# GPIO.net
KiCad netlist of a schematic drawn in Altium Designer
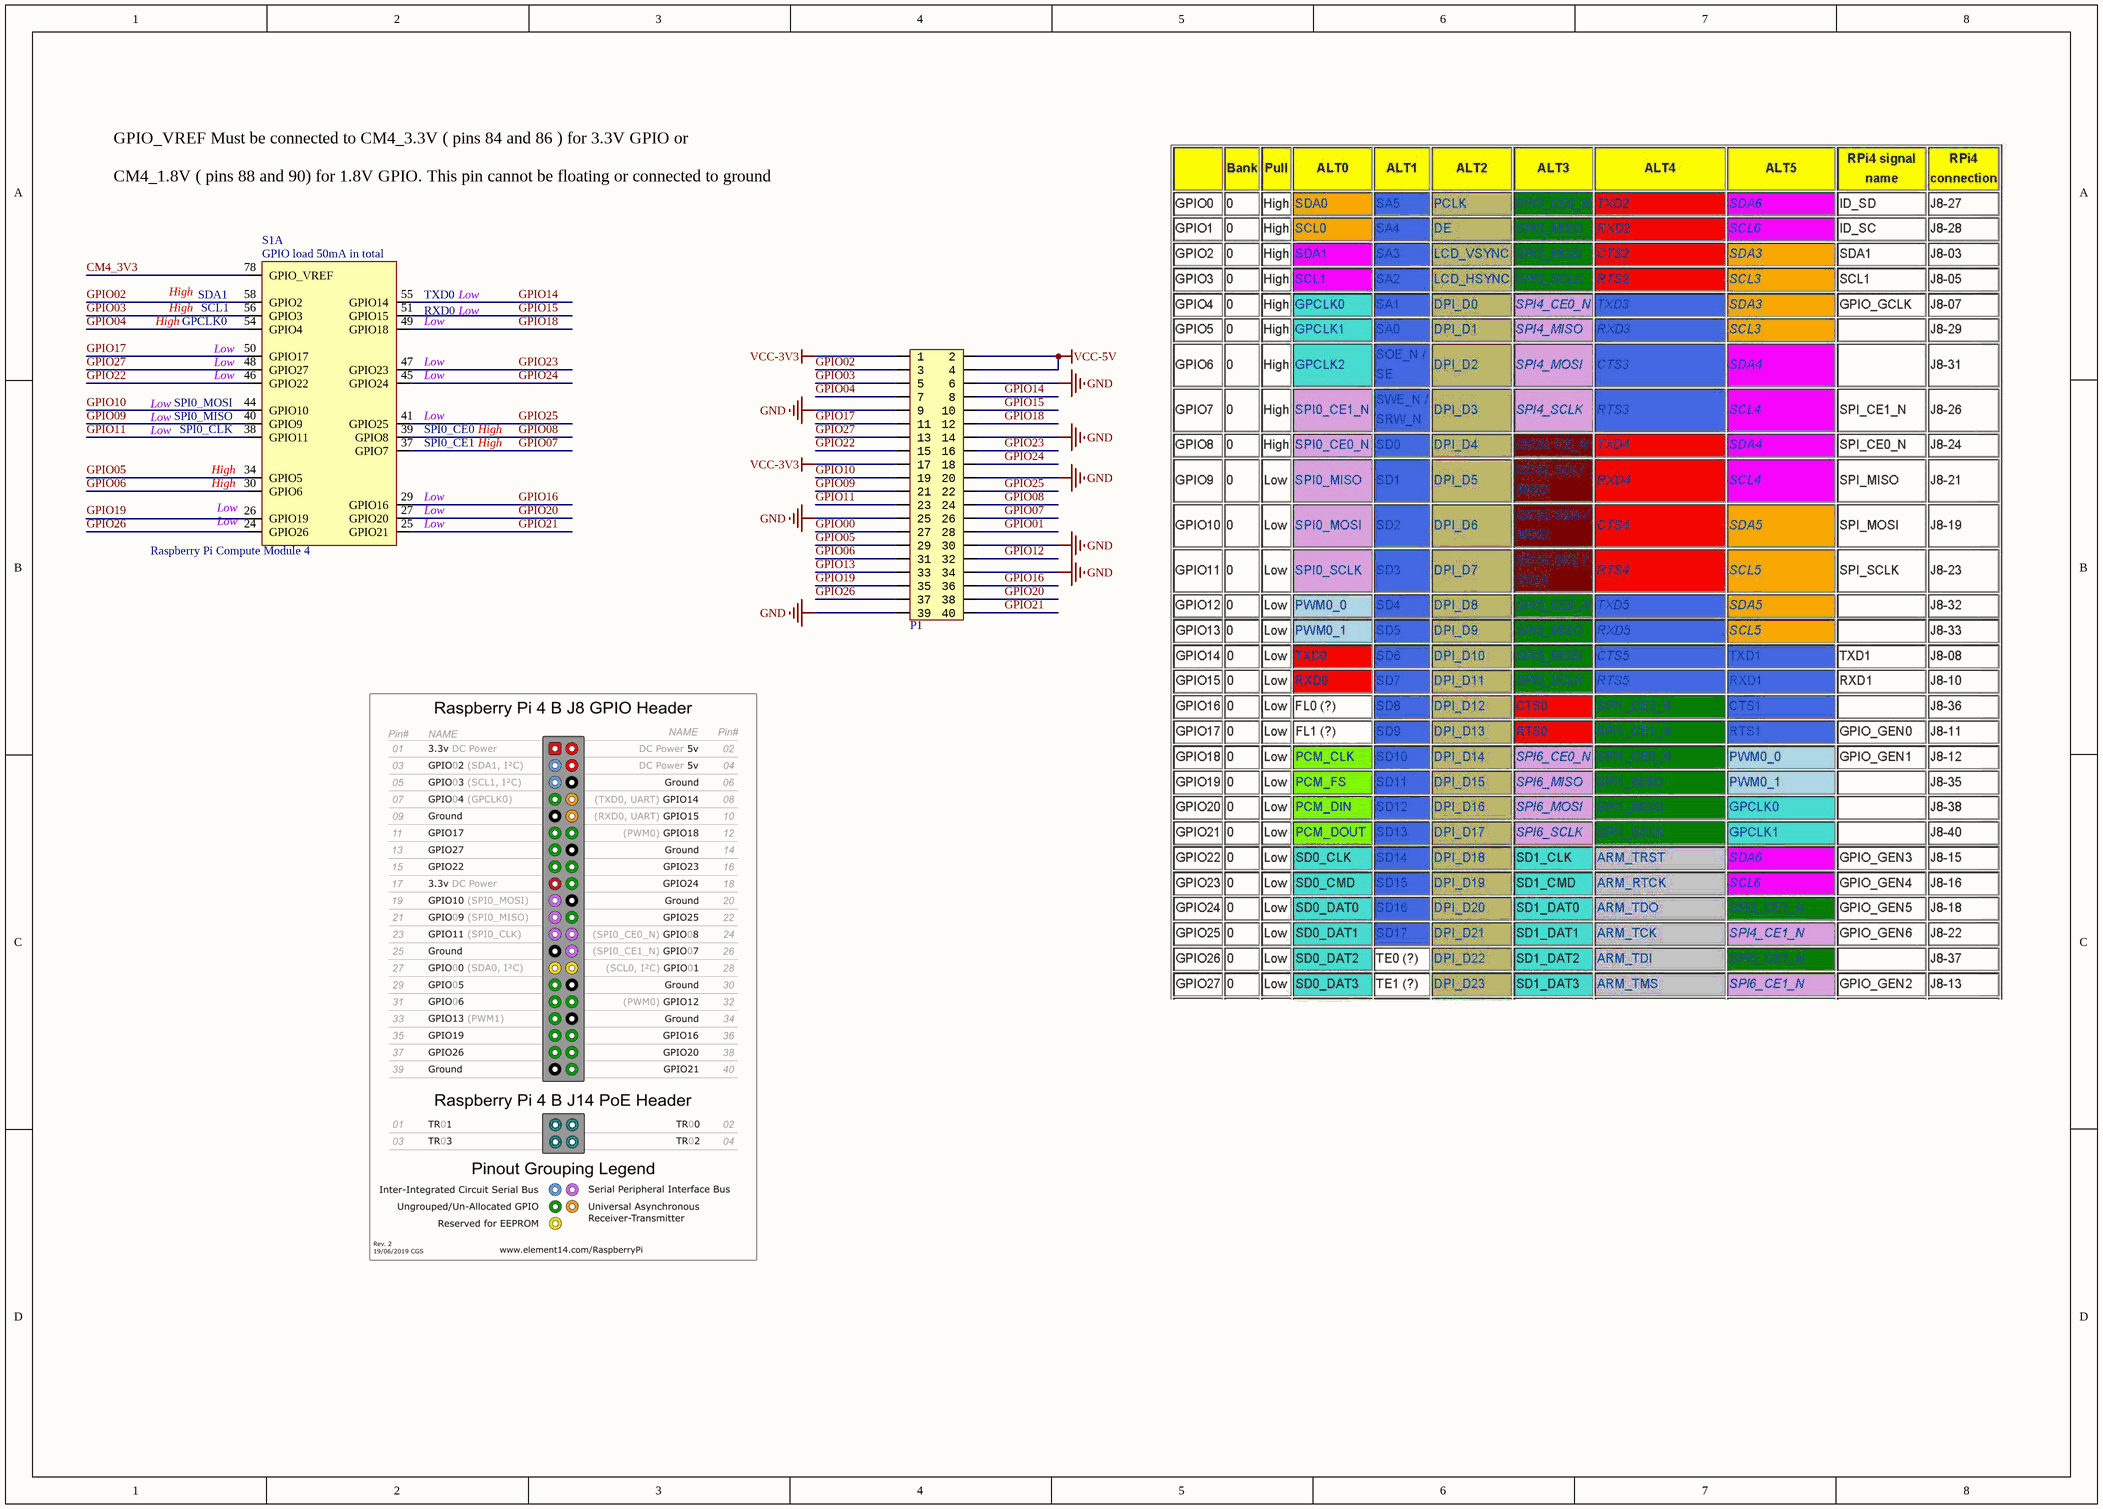
[diagram p0: GPIO.SchDoc]

(export (version "E")
  (design (tool "Eeschema 10.0.6"))
  (components
    (comp (ref "P1")
      (value "HDR2x20_2.54")
      (footprint "HDR2X20_2.54_180")
      (description "Header")
      (libsource (lib "KitSprout") (part "HDR2x20_2.54"))
    )
    (comp (ref "S1")
      (value "Raspberry Pi Compute Module 4")
      (footprint "CM4-DF40HC(3.0)-100DS-0.4v_3mm_1.5mm")
      (description "Raspberry Pi Compute Module 4 by Amornthep Phunsin")
      (libsource (lib "SOM") (part "CM4"))
    )
  )
  (nets
    (net (code "1") (name "/CM4_3V3") (class "Default")
      (node (ref "S1") (pin "78") (pinfunction "GPIO_VREF_78") (pintype "power_in"))
    )
    (net (code "2") (name "/GPIO00") (class "Default")
      (node (ref "P1") (pin "27") (pinfunction "27_27") (pintype "passive"))
    )
    (net (code "3") (name "/GPIO01") (class "Default")
      (node (ref "P1") (pin "28") (pinfunction "28_28") (pintype "passive"))
    )
    (net (code "4") (name "/GPIO02") (class "Default")
      (node (ref "P1") (pin "3") (pinfunction "3_3") (pintype "passive"))
      (node (ref "S1") (pin "58") (pinfunction "GPIO2_58") (pintype "passive"))
    )
    (net (code "5") (name "/GPIO03") (class "Default")
      (node (ref "P1") (pin "5") (pinfunction "5_5") (pintype "passive"))
      (node (ref "S1") (pin "56") (pinfunction "GPIO3_56") (pintype "passive"))
    )
    (net (code "6") (name "/GPIO04") (class "Default")
      (node (ref "P1") (pin "7") (pinfunction "7_7") (pintype "passive"))
      (node (ref "S1") (pin "54") (pinfunction "GPIO4_54") (pintype "passive"))
    )
    (net (code "7") (name "/GPIO05") (class "Default")
      (node (ref "P1") (pin "29") (pinfunction "29_29") (pintype "passive"))
      (node (ref "S1") (pin "34") (pinfunction "GPIO5_34") (pintype "passive"))
    )
    (net (code "8") (name "/GPIO06") (class "Default")
      (node (ref "P1") (pin "31") (pinfunction "31_31") (pintype "passive"))
      (node (ref "S1") (pin "30") (pinfunction "GPIO6_30") (pintype "passive"))
    )
    (net (code "9") (name "/GPIO07") (class "Default")
      (node (ref "P1") (pin "26") (pinfunction "26_26") (pintype "passive"))
      (node (ref "S1") (pin "37") (pinfunction "GPIO7_37") (pintype "passive"))
    )
    (net (code "10") (name "/GPIO08") (class "Default")
      (node (ref "P1") (pin "24") (pinfunction "24_24") (pintype "passive"))
      (node (ref "S1") (pin "39") (pinfunction "GPIO8_39") (pintype "passive"))
    )
    (net (code "11") (name "/GPIO09") (class "Default")
      (node (ref "P1") (pin "21") (pinfunction "21_21") (pintype "passive"))
      (node (ref "S1") (pin "40") (pinfunction "GPIO9_40") (pintype "passive"))
    )
    (net (code "12") (name "/GPIO10") (class "Default")
      (node (ref "P1") (pin "19") (pinfunction "19_19") (pintype "passive"))
      (node (ref "S1") (pin "44") (pinfunction "GPIO10_44") (pintype "passive"))
    )
    (net (code "13") (name "/GPIO11") (class "Default")
      (node (ref "P1") (pin "23") (pinfunction "23_23") (pintype "passive"))
      (node (ref "S1") (pin "38") (pinfunction "GPIO11_38") (pintype "passive"))
    )
    (net (code "14") (name "/GPIO12") (class "Default")
      (node (ref "P1") (pin "32") (pinfunction "32_32") (pintype "passive"))
    )
    (net (code "15") (name "/GPIO13") (class "Default")
      (node (ref "P1") (pin "33") (pinfunction "33_33") (pintype "passive"))
    )
    (net (code "16") (name "/GPIO14") (class "Default")
      (node (ref "P1") (pin "8") (pinfunction "8_8") (pintype "passive"))
      (node (ref "S1") (pin "55") (pinfunction "GPIO14_55") (pintype "passive"))
    )
    (net (code "17") (name "/GPIO15") (class "Default")
      (node (ref "P1") (pin "10") (pinfunction "10_10") (pintype "passive"))
      (node (ref "S1") (pin "51") (pinfunction "GPIO15_51") (pintype "passive"))
    )
    (net (code "18") (name "/GPIO16") (class "Default")
      (node (ref "P1") (pin "36") (pinfunction "36_36") (pintype "passive"))
      (node (ref "S1") (pin "29") (pinfunction "GPIO16_29") (pintype "passive"))
    )
    (net (code "19") (name "/GPIO17") (class "Default")
      (node (ref "P1") (pin "11") (pinfunction "11_11") (pintype "passive"))
      (node (ref "S1") (pin "50") (pinfunction "GPIO17_50") (pintype "passive"))
    )
    (net (code "20") (name "/GPIO18") (class "Default")
      (node (ref "P1") (pin "12") (pinfunction "12_12") (pintype "passive"))
      (node (ref "S1") (pin "49") (pinfunction "GPIO18_49") (pintype "passive"))
    )
    (net (code "21") (name "/GPIO19") (class "Default")
      (node (ref "P1") (pin "35") (pinfunction "35_35") (pintype "passive"))
      (node (ref "S1") (pin "26") (pinfunction "GPIO19_26") (pintype "passive"))
    )
    (net (code "22") (name "/GPIO20") (class "Default")
      (node (ref "P1") (pin "38") (pinfunction "38_38") (pintype "passive"))
      (node (ref "S1") (pin "27") (pinfunction "GPIO20_27") (pintype "passive"))
    )
    (net (code "23") (name "/GPIO21") (class "Default")
      (node (ref "P1") (pin "40") (pinfunction "40_40") (pintype "passive"))
      (node (ref "S1") (pin "25") (pinfunction "GPIO21_25") (pintype "passive"))
    )
    (net (code "24") (name "/GPIO22") (class "Default")
      (node (ref "P1") (pin "15") (pinfunction "15_15") (pintype "passive"))
      (node (ref "S1") (pin "46") (pinfunction "GPIO22_46") (pintype "passive"))
    )
    (net (code "25") (name "/GPIO23") (class "Default")
      (node (ref "P1") (pin "16") (pinfunction "16_16") (pintype "passive"))
      (node (ref "S1") (pin "47") (pinfunction "GPIO23_47") (pintype "passive"))
    )
    (net (code "26") (name "/GPIO24") (class "Default")
      (node (ref "P1") (pin "18") (pinfunction "18_18") (pintype "passive"))
      (node (ref "S1") (pin "45") (pinfunction "GPIO24_45") (pintype "passive"))
    )
    (net (code "27") (name "/GPIO25") (class "Default")
      (node (ref "P1") (pin "22") (pinfunction "22_22") (pintype "passive"))
      (node (ref "S1") (pin "41") (pinfunction "GPIO25_41") (pintype "passive"))
    )
    (net (code "28") (name "/GPIO26") (class "Default")
      (node (ref "P1") (pin "37") (pinfunction "37_37") (pintype "passive"))
      (node (ref "S1") (pin "24") (pinfunction "GPIO26_24") (pintype "passive"))
    )
    (net (code "29") (name "/GPIO27") (class "Default")
      (node (ref "P1") (pin "13") (pinfunction "13_13") (pintype "passive"))
      (node (ref "S1") (pin "48") (pinfunction "GPIO27_48") (pintype "passive"))
    )
    (net (code "30") (name "GND") (class "Default")
      (node (ref "P1") (pin "14") (pinfunction "14_14") (pintype "passive"))
      (node (ref "P1") (pin "20") (pinfunction "20_20") (pintype "passive"))
      (node (ref "P1") (pin "25") (pinfunction "25_25") (pintype "passive"))
      (node (ref "P1") (pin "30") (pinfunction "30_30") (pintype "passive"))
      (node (ref "P1") (pin "34") (pinfunction "34_34") (pintype "passive"))
      (node (ref "P1") (pin "39") (pinfunction "39_39") (pintype "passive"))
      (node (ref "P1") (pin "6") (pinfunction "6_6") (pintype "passive"))
      (node (ref "P1") (pin "9") (pinfunction "9_9") (pintype "passive"))
    )
    (net (code "31") (name "VCC-3V3") (class "Default")
      (node (ref "P1") (pin "1") (pinfunction "1_1") (pintype "passive"))
      (node (ref "P1") (pin "17") (pinfunction "17_17") (pintype "passive"))
    )
    (net (code "32") (name "VCC-5V") (class "Default")
      (node (ref "P1") (pin "2") (pinfunction "2_2") (pintype "passive"))
      (node (ref "P1") (pin "4") (pinfunction "4_4") (pintype "passive"))
    )
  )
)
